# 18650_1S1P_SMD.net
KiCad netlist of a schematic drawn in EAGLE
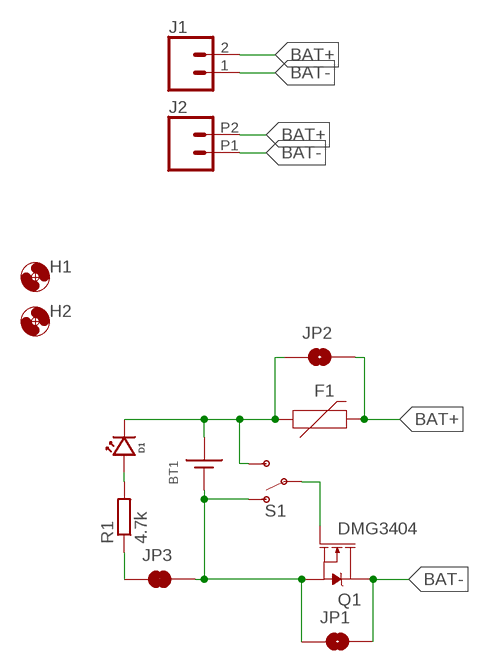
[diagram p0: schematic, sheet 1]

(export (version "E")
  (design (tool "Eeschema 10.0.6"))
  (components
    (comp (ref "BT1")
      (value "186501042P")
      (footprint "eagle-import:BATT_1042P")
      (libsource (lib "eagle-import") (part "186501042P"))
    )
    (comp (ref "D1")
      (value "LED0603")
      (footprint "eagle-import:LED_0603")
      (libsource (lib "eagle-import") (part "LED0603"))
    )
    (comp (ref "F1")
      (value "PPTC1.75A1210")
      (footprint "eagle-import:1210_BOURNS")
      (fields (field (name "MF") "Bourns") (field (name "MPN") "MF-USMF175X-2"))
      (libsource (lib "eagle-import") (part "PPTC12101.75A"))
    )
    (comp (ref "H1")
      (value "MOUNTING_HOLE4_NP")
      (footprint "eagle-import:4_40")
      (fields (field (name "MPN") "DNP"))
      (libsource (lib "eagle-import") (part "MOUNTING_HOLE4_NP"))
    )
    (comp (ref "H2")
      (value "MOUNTING_HOLE4_NP")
      (footprint "eagle-import:4_40")
      (fields (field (name "MPN") "DNP"))
      (libsource (lib "eagle-import") (part "MOUNTING_HOLE4_NP"))
    )
    (comp (ref "J1")
      (value "CONN_023.5MM_ROUND_RESTRICT")
      (footprint "eagle-import:SCREWTERMINAL-3.5MM-2_ROUND_RESTRICT")
      (fields (field (name "MF") "On Shore") (field (name "MPN") "OSTTE020161"))
      (libsource (lib "eagle-import") (part "CONN_023.5MM_ROUND_RESTRICT"))
    )
    (comp (ref "J2")
      (value "CONN_022.54_SCREW_ROUND")
      (footprint "eagle-import:1X02_2.54_SCREWTERM_ROUND")
      (fields (field (name "MF") "OnShore") (field (name "MPN") "OSTVN02A150"))
      (libsource (lib "eagle-import") (part "CONN_022.54_SCREW_ROUND"))
    )
    (comp (ref "JP1")
      (value "JUMPER-SMT_2_NO_SILK")
      (footprint "eagle-import:SMT-JUMPER_2_NO_SILK")
      (libsource (lib "eagle-import") (part "JUMPER-SMT_2_NO_SILK"))
    )
    (comp (ref "JP2")
      (value "JUMPER-SMT_2_NO_SILK")
      (footprint "eagle-import:SMT-JUMPER_2_NO_SILK")
      (libsource (lib "eagle-import") (part "JUMPER-SMT_2_NO_SILK"))
    )
    (comp (ref "JP3")
      (value "JUMPER-SMT_2_NC_TRACE_SILK")
      (footprint "eagle-import:SMT-JUMPER_2_NC_TRACE_SILK")
      (libsource (lib "eagle-import") (part "JUMPER-SMT_2_NC_TRACE_SILK"))
    )
    (comp (ref "Q1")
      (value "DMG3404")
      (footprint "eagle-import:SOT23-3")
      (fields (field (name "MF") "Diodes Incorporated") (field (name "MPN") "DMG3404L-7"))
      (libsource (lib "eagle-import") (part "MOSFET-NCH-DMG3404L"))
    )
    (comp (ref "R1")
      (value "4.7k")
      (footprint "eagle-import:R0603")
      (fields (field (name "MF") "Yageo") (field (name "MPN") "RC0603FR-074K7L"))
      (libsource (lib "eagle-import") (part "R-EU_R06034.7K"))
    )
    (comp (ref "S1")
      (value "SPDTOS1020")
      (footprint "eagle-import:OS102011MS2QN1")
      (libsource (lib "eagle-import") (part "SPDTOS1020"))
    )
  )
  (nets
    (net (code "1") (name "BAT+") (class "Default")
      (node (ref "F1") (pin "2") (pinfunction "2_2") (pintype "bidirectional"))
      (node (ref "J1") (pin "2") (pinfunction "2_2") (pintype "passive"))
      (node (ref "J2") (pin "P2") (pinfunction "2_P2") (pintype "passive"))
      (node (ref "JP2") (pin "2") (pinfunction "2_2") (pintype "passive"))
    )
    (net (code "2") (name "BAT-") (class "Default")
      (node (ref "J1") (pin "1") (pinfunction "1_1") (pintype "passive"))
      (node (ref "J2") (pin "P1") (pinfunction "1_P1") (pintype "passive"))
      (node (ref "JP1") (pin "2") (pinfunction "2_2") (pintype "passive"))
      (node (ref "Q1") (pin "3") (pinfunction "D_3") (pintype "bidirectional"))
    )
    (net (code "3") (name "Net-(BT1-+)") (class "Default")
      (node (ref "BT1") (pin "BATT+") (pinfunction "+_BATT+") (pintype "power_in"))
      (node (ref "D1") (pin "CATHODE") (pinfunction "CATHODE_CATHODE") (pintype "power_in"))
      (node (ref "F1") (pin "1") (pinfunction "1_1") (pintype "bidirectional"))
      (node (ref "JP2") (pin "1") (pinfunction "1_1") (pintype "passive"))
      (node (ref "S1") (pin "3") (pinfunction "S_3") (pintype "passive"))
    )
    (net (code "4") (name "Net-(BT1--)") (class "Default")
      (node (ref "BT1") (pin "BATT-") (pinfunction "-_BATT-") (pintype "power_in"))
      (node (ref "JP1") (pin "1") (pinfunction "1_1") (pintype "passive"))
      (node (ref "JP3") (pin "2") (pinfunction "2_2") (pintype "passive"))
      (node (ref "Q1") (pin "2") (pinfunction "S_2") (pintype "bidirectional"))
      (node (ref "S1") (pin "1") (pinfunction "O_1") (pintype "passive"))
    )
    (net (code "5") (name "Net-(D1-PadANODE)") (class "Default")
      (node (ref "D1") (pin "ANODE") (pinfunction "ANODE_ANODE") (pintype "power_in"))
      (node (ref "R1") (pin "2") (pinfunction "2_2") (pintype "passive"))
    )
    (net (code "6") (name "Net-(JP3-Pad1)") (class "Default")
      (node (ref "JP3") (pin "1") (pinfunction "1_1") (pintype "passive"))
      (node (ref "R1") (pin "1") (pinfunction "1_1") (pintype "passive"))
    )
    (net (code "7") (name "Net-(Q1-G)") (class "Default")
      (node (ref "Q1") (pin "1") (pinfunction "G_1") (pintype "bidirectional"))
      (node (ref "S1") (pin "2") (pinfunction "P_2") (pintype "passive"))
    )
  )
)
